# SparkFun_Beefcake_Relay_Control_Kit.net
KiCad netlist of a schematic drawn in EAGLE
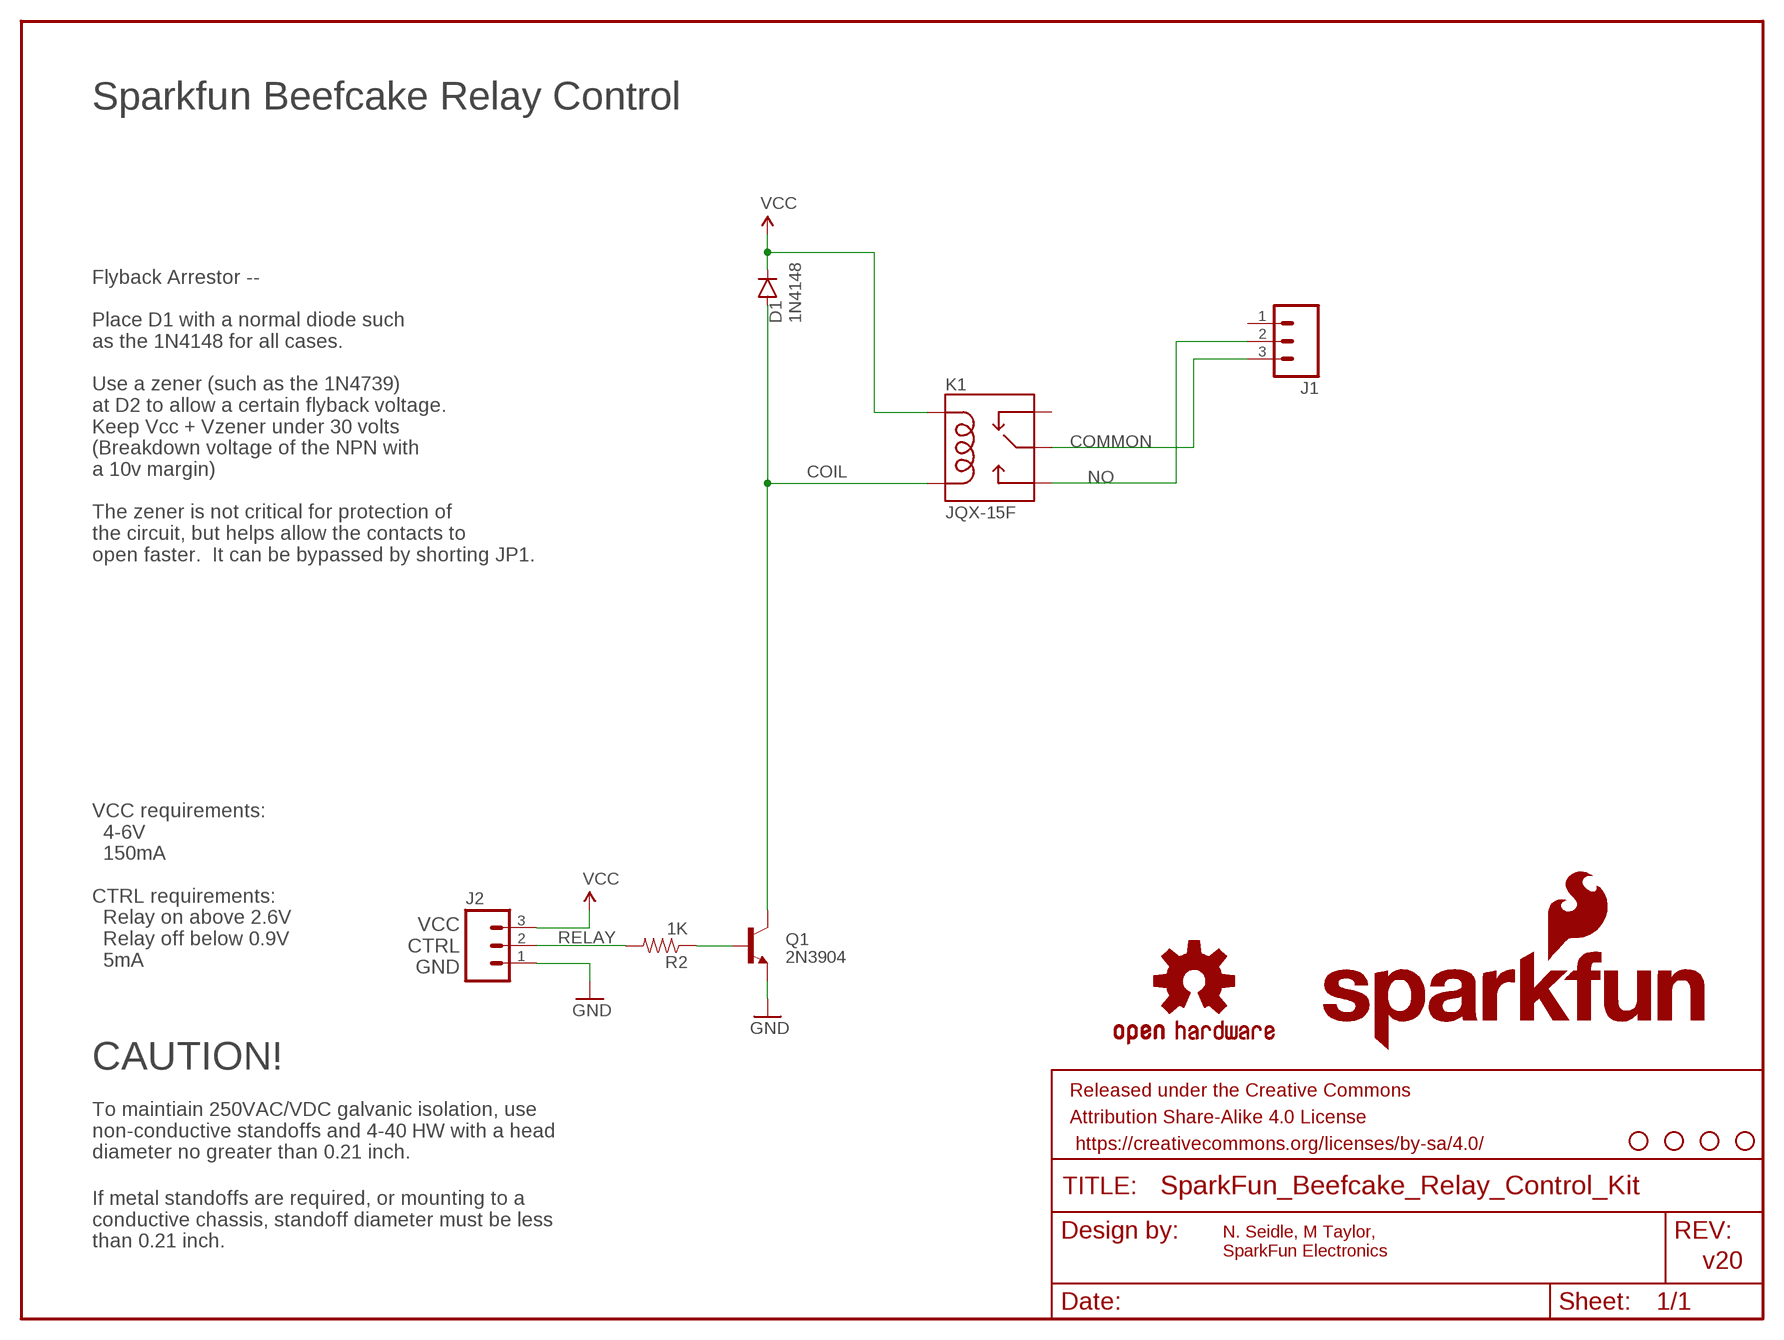
[diagram p0: schematic, sheet 1]

(export (version "E")
  (design (tool "Eeschema 10.0.6"))
  (components
    (comp (ref "D1")
      (value "1N4148")
      (footprint "eagle-import:DIODE-1N4148-KIT")
      (libsource (lib "eagle-import") (part "DIODEKIT"))
    )
    (comp (ref "FRAME2")
      (value "FRAME-LETTER")
      (footprint "eagle-import:CREATIVE_COMMONS")
      (libsource (lib "eagle-import") (part "FRAME-LETTER"))
    )
    (comp (ref "J1")
      (value "M03-SCREW-5MM")
      (footprint "eagle-import:SCREWTERMINAL-5MM-3")
      (libsource (lib "eagle-import") (part "M03-SCREW-5MM"))
    )
    (comp (ref "J2")
      (value "M03SCREW")
      (footprint "eagle-import:SCREWTERMINAL-3.5MM-3")
      (libsource (lib "eagle-import") (part "M03SCREW"))
    )
    (comp (ref "K1")
      (value "JQX-15F")
      (footprint "eagle-import:RELAY-T90")
      (libsource (lib "eagle-import") (part "RELAYPTH5"))
    )
    (comp (ref "LOGO1")
      (value "SFE_LOGO_NAME_FLAME.1_INCH")
      (footprint "eagle-import:SFE_LOGO_NAME_FLAME_.1")
      (libsource (lib "eagle-import") (part "SFE_LOGO_NAME_FLAME.1_INCH"))
    )
    (comp (ref "Q1")
      (value "2N3904")
      (footprint "eagle-import:TO-92-EZ")
      (libsource (lib "eagle-import") (part "TRANSISTOR_NPN2N3904-EZ"))
    )
    (comp (ref "R2")
      (value "1K")
      (footprint "eagle-import:AXIAL-0.3EZ")
      (libsource (lib "eagle-import") (part "1KOHM-1/4W-1%(PTH)HORIZ-KIT"))
    )
    (comp (ref "U$3")
      (value "STAND-OFF")
      (footprint "eagle-import:STAND-OFF")
      (libsource (lib "eagle-import") (part "STAND-OFF"))
    )
    (comp (ref "U$4")
      (value "STAND-OFF")
      (footprint "eagle-import:STAND-OFF")
      (libsource (lib "eagle-import") (part "STAND-OFF"))
    )
    (comp (ref "U$5")
      (value "STAND-OFF")
      (footprint "eagle-import:STAND-OFF")
      (libsource (lib "eagle-import") (part "STAND-OFF"))
    )
    (comp (ref "U$7")
      (value "STAND-OFF")
      (footprint "eagle-import:STAND-OFF")
      (libsource (lib "eagle-import") (part "STAND-OFF"))
    )
    (comp (ref "U$12")
      (value "OSHW-LOGOS")
      (footprint "eagle-import:OSHW-LOGO-S")
      (libsource (lib "eagle-import") (part "OSHW-LOGOS"))
    )
  )
  (nets
    (net (code "1") (name "/COIL") (class "Default")
      (node (ref "D1") (pin "A") (pinfunction "A_A") (pintype "passive"))
      (node (ref "K1") (pin "COIL2") (pinfunction "COIL2_COIL2") (pintype "bidirectional"))
      (node (ref "Q1") (pin "3") (pinfunction "C_3") (pintype "passive"))
    )
    (net (code "2") (name "/COMMON") (class "Default")
      (node (ref "J1") (pin "3") (pinfunction "3_3") (pintype "passive"))
      (node (ref "K1") (pin "MAIN") (pinfunction "MAIN_MAIN") (pintype "bidirectional"))
    )
    (net (code "3") (name "/NO") (class "Default")
      (node (ref "J1") (pin "2") (pinfunction "2_2") (pintype "passive"))
      (node (ref "K1") (pin "NO") (pinfunction "NO_NO") (pintype "bidirectional"))
    )
    (net (code "4") (name "/RELAY") (class "Default")
      (node (ref "J2") (pin "2") (pinfunction "2_2") (pintype "passive"))
      (node (ref "R2") (pin "P$2") (pinfunction "2_P$2") (pintype "passive"))
    )
    (net (code "5") (name "GND") (class "Default")
      (node (ref "J2") (pin "1") (pinfunction "1_1") (pintype "passive"))
      (node (ref "Q1") (pin "1") (pinfunction "E_1") (pintype "passive"))
    )
    (net (code "6") (name "Net-(Q1-B)") (class "Default")
      (node (ref "Q1") (pin "2") (pinfunction "B_2") (pintype "passive"))
      (node (ref "R2") (pin "P$1") (pinfunction "1_P$1") (pintype "passive"))
    )
    (net (code "7") (name "VCC") (class "Default")
      (node (ref "D1") (pin "C") (pinfunction "C_C") (pintype "passive"))
      (node (ref "J2") (pin "3") (pinfunction "3_3") (pintype "passive"))
      (node (ref "K1") (pin "COIL1") (pinfunction "COIL1_COIL1") (pintype "bidirectional"))
    )
    (net (code "8") (name "unconnected-(J1-Pad1)") (class "Default")
      (node (ref "J1") (pin "1") (pinfunction "1_1") (pintype "passive"))
    )
    (net (code "9") (name "unconnected-(K1-PadNC)") (class "Default")
      (node (ref "K1") (pin "NC") (pinfunction "NC_NC") (pintype "bidirectional"))
    )
  )
)
